# stratum1.net
KiCad netlist of a schematic drawn in EAGLE
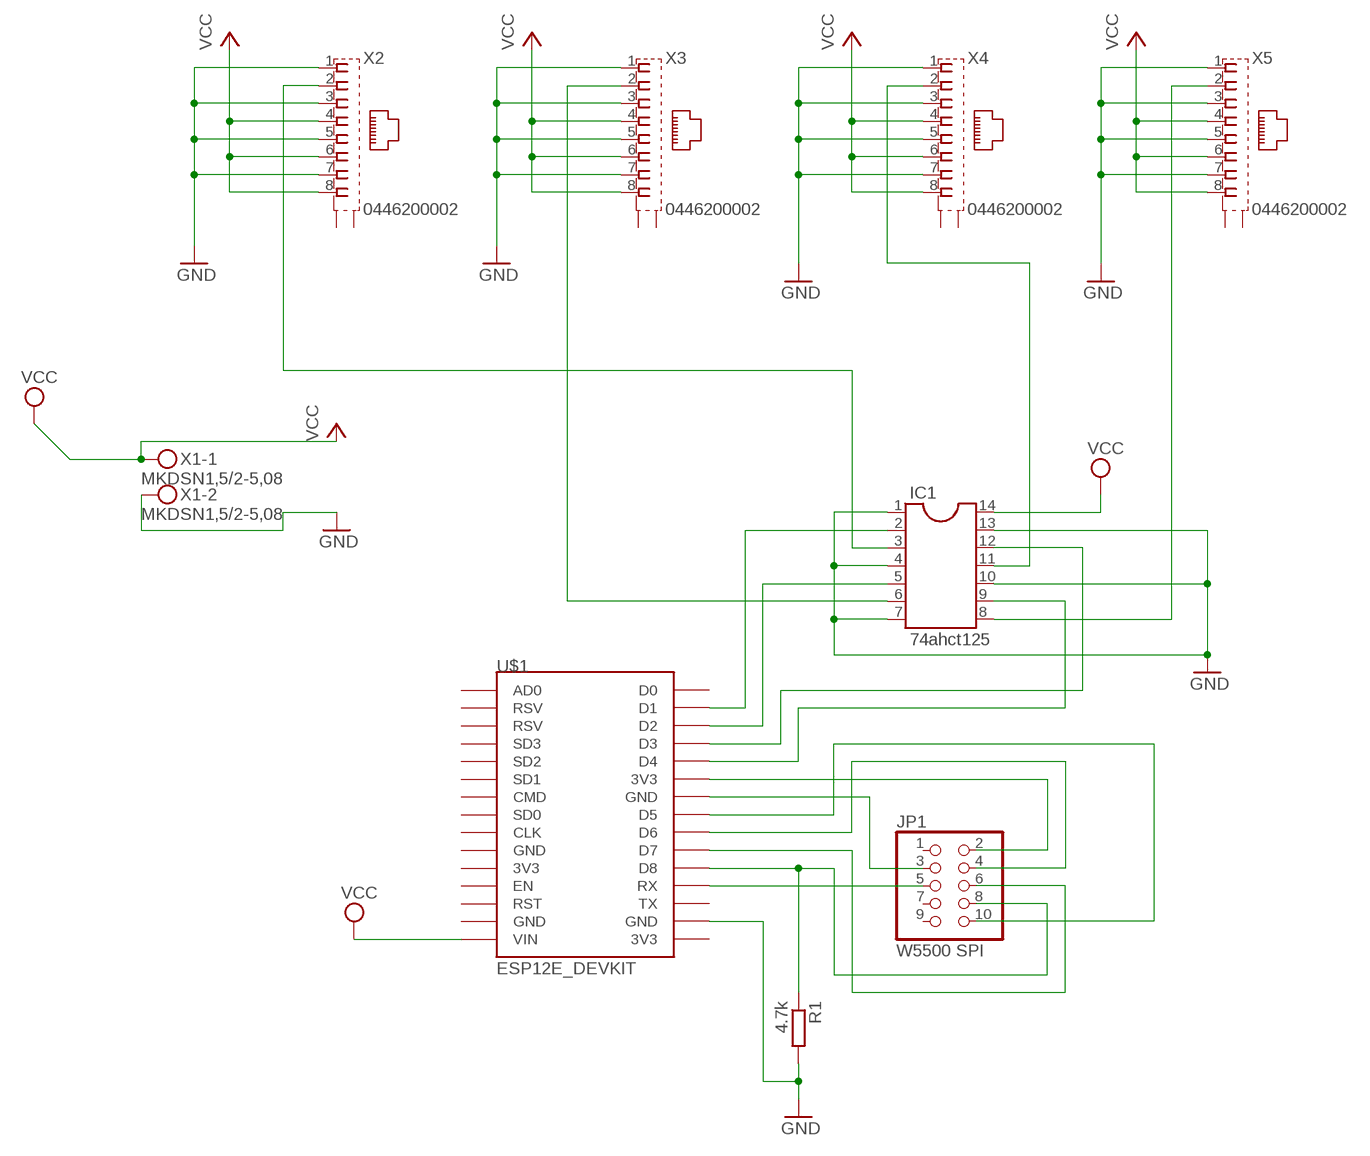
[diagram p0: schematic, sheet 1]

(export (version "E")
  (design (tool "Eeschema 10.0.6"))
  (components
    (comp (ref "IC1")
      (value "74ahct125")
      (footprint "eagle-import:DIL14")
      (fields (field (name "MF") "TEXAS INSTRUMENT CONNECTORS") (field (name "MPN") "SN74AHCT125N"))
      (libsource (lib "eagle-import") (part "DIL14"))
    )
    (comp (ref "JP1")
      (value "W5500 SPI")
      (footprint "eagle-import:2X05")
      (libsource (lib "eagle-import") (part "PINHD-2X5"))
    )
    (comp (ref "R1")
      (value "4.7k")
      (footprint "eagle-import:0207_10")
      (fields (field (name "MPN") "MCWF08P4701FTL"))
      (libsource (lib "eagle-import") (part "R-EU_0207/10"))
    )
    (comp (ref "U$1")
      (value "ESP12E_DEVKIT")
      (footprint "eagle-import:ESP12E_DEVKIT")
      (libsource (lib "eagle-import") (part "ESP12E_DEVKIT"))
    )
    (comp (ref "X1")
      (value "MKDSN1,5/2-5,08")
      (footprint "eagle-import:MKDSN1,5_2-5,08")
      (fields (field (name "OC_NEWARK") "unknown"))
      (libsource (lib "eagle-import") (part "MKDSN1,5/2-5,08"))
    )
    (comp (ref "X2")
      (value "0446200002")
      (footprint "eagle-import:0446200002")
      (fields (field (name "MF") "MOLEX") (field (name "MF_1") "FARNELL"))
      (libsource (lib "eagle-import") (part "0446200002"))
    )
    (comp (ref "X3")
      (value "0446200002")
      (footprint "eagle-import:0446200002")
      (fields (field (name "MF") "MOLEX") (field (name "MF_1") "FARNELL"))
      (libsource (lib "eagle-import") (part "0446200002"))
    )
    (comp (ref "X4")
      (value "0446200002")
      (footprint "eagle-import:0446200002")
      (fields (field (name "MF") "MOLEX") (field (name "MF_1") "FARNELL"))
      (libsource (lib "eagle-import") (part "0446200002"))
    )
    (comp (ref "X5")
      (value "0446200002")
      (footprint "eagle-import:0446200002")
      (fields (field (name "MF") "MOLEX") (field (name "MF_1") "FARNELL"))
      (libsource (lib "eagle-import") (part "0446200002"))
    )
  )
  (nets
    (net (code "1") (name "GND") (class "Default")
      (node (ref "IC1") (pin "1") (pinfunction "1_1") (pintype "passive"))
      (node (ref "IC1") (pin "10") (pinfunction "10_10") (pintype "passive"))
      (node (ref "IC1") (pin "13") (pinfunction "13_13") (pintype "passive"))
      (node (ref "IC1") (pin "4") (pinfunction "4_4") (pintype "passive"))
      (node (ref "IC1") (pin "7") (pinfunction "7_7") (pintype "passive"))
      (node (ref "R1") (pin "2") (pinfunction "2_2") (pintype "passive"))
      (node (ref "U$1") (pin "GND@3") (pinfunction "GND_GND@3") (pintype "bidirectional"))
      (node (ref "X1") (pin "2") (pinfunction "KL_2") (pintype "passive"))
      (node (ref "X2") (pin "1") (pinfunction "1_1") (pintype "passive"))
      (node (ref "X2") (pin "3") (pinfunction "3_3") (pintype "passive"))
      (node (ref "X2") (pin "5") (pinfunction "5_5") (pintype "passive"))
      (node (ref "X2") (pin "7") (pinfunction "7_7") (pintype "passive"))
      (node (ref "X3") (pin "1") (pinfunction "1_1") (pintype "passive"))
      (node (ref "X3") (pin "3") (pinfunction "3_3") (pintype "passive"))
      (node (ref "X3") (pin "5") (pinfunction "5_5") (pintype "passive"))
      (node (ref "X3") (pin "7") (pinfunction "7_7") (pintype "passive"))
      (node (ref "X4") (pin "1") (pinfunction "1_1") (pintype "passive"))
      (node (ref "X4") (pin "3") (pinfunction "3_3") (pintype "passive"))
      (node (ref "X4") (pin "5") (pinfunction "5_5") (pintype "passive"))
      (node (ref "X4") (pin "7") (pinfunction "7_7") (pintype "passive"))
      (node (ref "X5") (pin "1") (pinfunction "1_1") (pintype "passive"))
      (node (ref "X5") (pin "3") (pinfunction "3_3") (pintype "passive"))
      (node (ref "X5") (pin "5") (pinfunction "5_5") (pintype "passive"))
      (node (ref "X5") (pin "7") (pinfunction "7_7") (pintype "passive"))
    )
    (net (code "2") (name "Net-(IC1-Pad2)") (class "Default")
      (node (ref "IC1") (pin "2") (pinfunction "2_2") (pintype "passive"))
      (node (ref "U$1") (pin "D1") (pinfunction "D1_D1") (pintype "bidirectional"))
    )
    (net (code "3") (name "Net-(IC1-Pad3)") (class "Default")
      (node (ref "IC1") (pin "3") (pinfunction "3_3") (pintype "passive"))
      (node (ref "X2") (pin "2") (pinfunction "2_2") (pintype "passive"))
    )
    (net (code "4") (name "Net-(IC1-Pad5)") (class "Default")
      (node (ref "IC1") (pin "5") (pinfunction "5_5") (pintype "passive"))
      (node (ref "U$1") (pin "D2") (pinfunction "D2_D2") (pintype "bidirectional"))
    )
    (net (code "5") (name "Net-(IC1-Pad6)") (class "Default")
      (node (ref "IC1") (pin "6") (pinfunction "6_6") (pintype "passive"))
      (node (ref "X3") (pin "2") (pinfunction "2_2") (pintype "passive"))
    )
    (net (code "6") (name "Net-(IC1-Pad8)") (class "Default")
      (node (ref "IC1") (pin "8") (pinfunction "8_8") (pintype "passive"))
      (node (ref "X5") (pin "2") (pinfunction "2_2") (pintype "passive"))
    )
    (net (code "7") (name "Net-(IC1-Pad9)") (class "Default")
      (node (ref "IC1") (pin "9") (pinfunction "9_9") (pintype "passive"))
      (node (ref "U$1") (pin "D4") (pinfunction "D4_D4") (pintype "bidirectional"))
    )
    (net (code "8") (name "Net-(IC1-Pad11)") (class "Default")
      (node (ref "IC1") (pin "11") (pinfunction "11_11") (pintype "passive"))
      (node (ref "X4") (pin "2") (pinfunction "2_2") (pintype "passive"))
    )
    (net (code "9") (name "Net-(IC1-Pad12)") (class "Default")
      (node (ref "IC1") (pin "12") (pinfunction "12_12") (pintype "passive"))
      (node (ref "U$1") (pin "D3") (pinfunction "D3_D3") (pintype "bidirectional"))
    )
    (net (code "10") (name "Net-(JP1-Pad2)") (class "Default")
      (node (ref "JP1") (pin "2") (pinfunction "2_2") (pintype "passive"))
      (node (ref "U$1") (pin "3V3@1") (pinfunction "3V3_3V3@1") (pintype "bidirectional"))
    )
    (net (code "11") (name "Net-(JP1-Pad3)") (class "Default")
      (node (ref "JP1") (pin "3") (pinfunction "3_3") (pintype "passive"))
      (node (ref "U$1") (pin "GND@2") (pinfunction "GND_GND@2") (pintype "bidirectional"))
    )
    (net (code "12") (name "Net-(JP1-Pad4)") (class "Default")
      (node (ref "JP1") (pin "4") (pinfunction "4_4") (pintype "passive"))
      (node (ref "U$1") (pin "D6") (pinfunction "D6_D6") (pintype "bidirectional"))
    )
    (net (code "13") (name "Net-(JP1-Pad5)") (class "Default")
      (node (ref "JP1") (pin "5") (pinfunction "5_5") (pintype "passive"))
      (node (ref "U$1") (pin "RX") (pinfunction "RX_RX") (pintype "bidirectional"))
    )
    (net (code "14") (name "Net-(JP1-Pad6)") (class "Default")
      (node (ref "JP1") (pin "6") (pinfunction "6_6") (pintype "passive"))
      (node (ref "U$1") (pin "D7") (pinfunction "D7_D7") (pintype "bidirectional"))
    )
    (net (code "15") (name "Net-(JP1-Pad8)") (class "Default")
      (node (ref "JP1") (pin "8") (pinfunction "8_8") (pintype "passive"))
      (node (ref "R1") (pin "1") (pinfunction "1_1") (pintype "passive"))
      (node (ref "U$1") (pin "D8") (pinfunction "D8_D8") (pintype "bidirectional"))
    )
    (net (code "16") (name "Net-(JP1-Pad10)") (class "Default")
      (node (ref "JP1") (pin "10") (pinfunction "10_10") (pintype "passive"))
      (node (ref "U$1") (pin "D5") (pinfunction "D5_D5") (pintype "bidirectional"))
    )
    (net (code "17") (name "VCC") (class "Default")
      (node (ref "IC1") (pin "14") (pinfunction "14_14") (pintype "passive"))
      (node (ref "U$1") (pin "VIN") (pinfunction "VIN_VIN") (pintype "bidirectional"))
      (node (ref "X1") (pin "1") (pinfunction "KL_1") (pintype "passive"))
      (node (ref "X2") (pin "4") (pinfunction "4_4") (pintype "passive"))
      (node (ref "X2") (pin "6") (pinfunction "6_6") (pintype "passive"))
      (node (ref "X2") (pin "8") (pinfunction "8_8") (pintype "passive"))
      (node (ref "X3") (pin "4") (pinfunction "4_4") (pintype "passive"))
      (node (ref "X3") (pin "6") (pinfunction "6_6") (pintype "passive"))
      (node (ref "X3") (pin "8") (pinfunction "8_8") (pintype "passive"))
      (node (ref "X4") (pin "4") (pinfunction "4_4") (pintype "passive"))
      (node (ref "X4") (pin "6") (pinfunction "6_6") (pintype "passive"))
      (node (ref "X4") (pin "8") (pinfunction "8_8") (pintype "passive"))
      (node (ref "X5") (pin "4") (pinfunction "4_4") (pintype "passive"))
      (node (ref "X5") (pin "6") (pinfunction "6_6") (pintype "passive"))
      (node (ref "X5") (pin "8") (pinfunction "8_8") (pintype "passive"))
    )
    (net (code "18") (name "unconnected-(JP1-Pad1)") (class "Default")
      (node (ref "JP1") (pin "1") (pinfunction "1_1") (pintype "passive"))
    )
    (net (code "19") (name "unconnected-(JP1-Pad7)") (class "Default")
      (node (ref "JP1") (pin "7") (pinfunction "7_7") (pintype "passive"))
    )
    (net (code "20") (name "unconnected-(JP1-Pad9)") (class "Default")
      (node (ref "JP1") (pin "9") (pinfunction "9_9") (pintype "passive"))
    )
    (net (code "21") (name "unconnected-(U$1-3V3-Pad3V3@0)") (class "Default")
      (node (ref "U$1") (pin "3V3@0") (pinfunction "3V3_3V3@0") (pintype "bidirectional"))
    )
    (net (code "22") (name "unconnected-(U$1-3V3-Pad3V3@2)") (class "Default")
      (node (ref "U$1") (pin "3V3@2") (pinfunction "3V3_3V3@2") (pintype "bidirectional"))
    )
    (net (code "23") (name "unconnected-(U$1-GND-PadGND@0)") (class "Default")
      (node (ref "U$1") (pin "GND@0") (pinfunction "GND_GND@0") (pintype "bidirectional"))
    )
    (net (code "24") (name "unconnected-(U$1-GND-PadGND@1)") (class "Default")
      (node (ref "U$1") (pin "GND@1") (pinfunction "GND_GND@1") (pintype "bidirectional"))
    )
    (net (code "25") (name "unconnected-(U$1-PadAD0)") (class "Default")
      (node (ref "U$1") (pin "AD0") (pinfunction "AD0_AD0") (pintype "bidirectional"))
    )
    (net (code "26") (name "unconnected-(U$1-PadCLK)") (class "Default")
      (node (ref "U$1") (pin "CLK") (pinfunction "CLK_CLK") (pintype "bidirectional"))
    )
    (net (code "27") (name "unconnected-(U$1-PadCMD)") (class "Default")
      (node (ref "U$1") (pin "CMD") (pinfunction "CMD_CMD") (pintype "bidirectional"))
    )
    (net (code "28") (name "unconnected-(U$1-PadD0)") (class "Default")
      (node (ref "U$1") (pin "D0") (pinfunction "D0_D0") (pintype "bidirectional"))
    )
    (net (code "29") (name "unconnected-(U$1-PadEN)") (class "Default")
      (node (ref "U$1") (pin "EN") (pinfunction "EN_EN") (pintype "bidirectional"))
    )
    (net (code "30") (name "unconnected-(U$1-PadRST)") (class "Default")
      (node (ref "U$1") (pin "RST") (pinfunction "RST_RST") (pintype "bidirectional"))
    )
    (net (code "31") (name "unconnected-(U$1-PadSD0)") (class "Default")
      (node (ref "U$1") (pin "SD0") (pinfunction "SD0_SD0") (pintype "bidirectional"))
    )
    (net (code "32") (name "unconnected-(U$1-PadSD1)") (class "Default")
      (node (ref "U$1") (pin "SD1") (pinfunction "SD1_SD1") (pintype "bidirectional"))
    )
    (net (code "33") (name "unconnected-(U$1-PadSD2)") (class "Default")
      (node (ref "U$1") (pin "SD2") (pinfunction "SD2_SD2") (pintype "bidirectional"))
    )
    (net (code "34") (name "unconnected-(U$1-PadSD3)") (class "Default")
      (node (ref "U$1") (pin "SD3") (pinfunction "SD3_SD3") (pintype "bidirectional"))
    )
    (net (code "35") (name "unconnected-(U$1-PadTX)") (class "Default")
      (node (ref "U$1") (pin "TX") (pinfunction "TX_TX") (pintype "bidirectional"))
    )
    (net (code "36") (name "unconnected-(U$1-RSV-PadRSV@0)") (class "Default")
      (node (ref "U$1") (pin "RSV@0") (pinfunction "RSV_RSV@0") (pintype "bidirectional"))
    )
    (net (code "37") (name "unconnected-(U$1-RSV-PadRSV@1)") (class "Default")
      (node (ref "U$1") (pin "RSV@1") (pinfunction "RSV_RSV@1") (pintype "bidirectional"))
    )
    (net (code "38") (name "unconnected-(X2-S1-PadS@1)") (class "Default")
      (node (ref "X2") (pin "S@1") (pinfunction "S1_S@1") (pintype "passive"))
    )
    (net (code "39") (name "unconnected-(X2-S2-PadS@2)") (class "Default")
      (node (ref "X2") (pin "S@2") (pinfunction "S2_S@2") (pintype "passive"))
    )
    (net (code "40") (name "unconnected-(X3-S1-PadS@1)") (class "Default")
      (node (ref "X3") (pin "S@1") (pinfunction "S1_S@1") (pintype "passive"))
    )
    (net (code "41") (name "unconnected-(X3-S2-PadS@2)") (class "Default")
      (node (ref "X3") (pin "S@2") (pinfunction "S2_S@2") (pintype "passive"))
    )
    (net (code "42") (name "unconnected-(X4-S1-PadS@1)") (class "Default")
      (node (ref "X4") (pin "S@1") (pinfunction "S1_S@1") (pintype "passive"))
    )
    (net (code "43") (name "unconnected-(X4-S2-PadS@2)") (class "Default")
      (node (ref "X4") (pin "S@2") (pinfunction "S2_S@2") (pintype "passive"))
    )
    (net (code "44") (name "unconnected-(X5-S1-PadS@1)") (class "Default")
      (node (ref "X5") (pin "S@1") (pinfunction "S1_S@1") (pintype "passive"))
    )
    (net (code "45") (name "unconnected-(X5-S2-PadS@2)") (class "Default")
      (node (ref "X5") (pin "S@2") (pinfunction "S2_S@2") (pintype "passive"))
    )
  )
)
